# usbtomidi.net
KiCad netlist of a schematic drawn in EAGLE
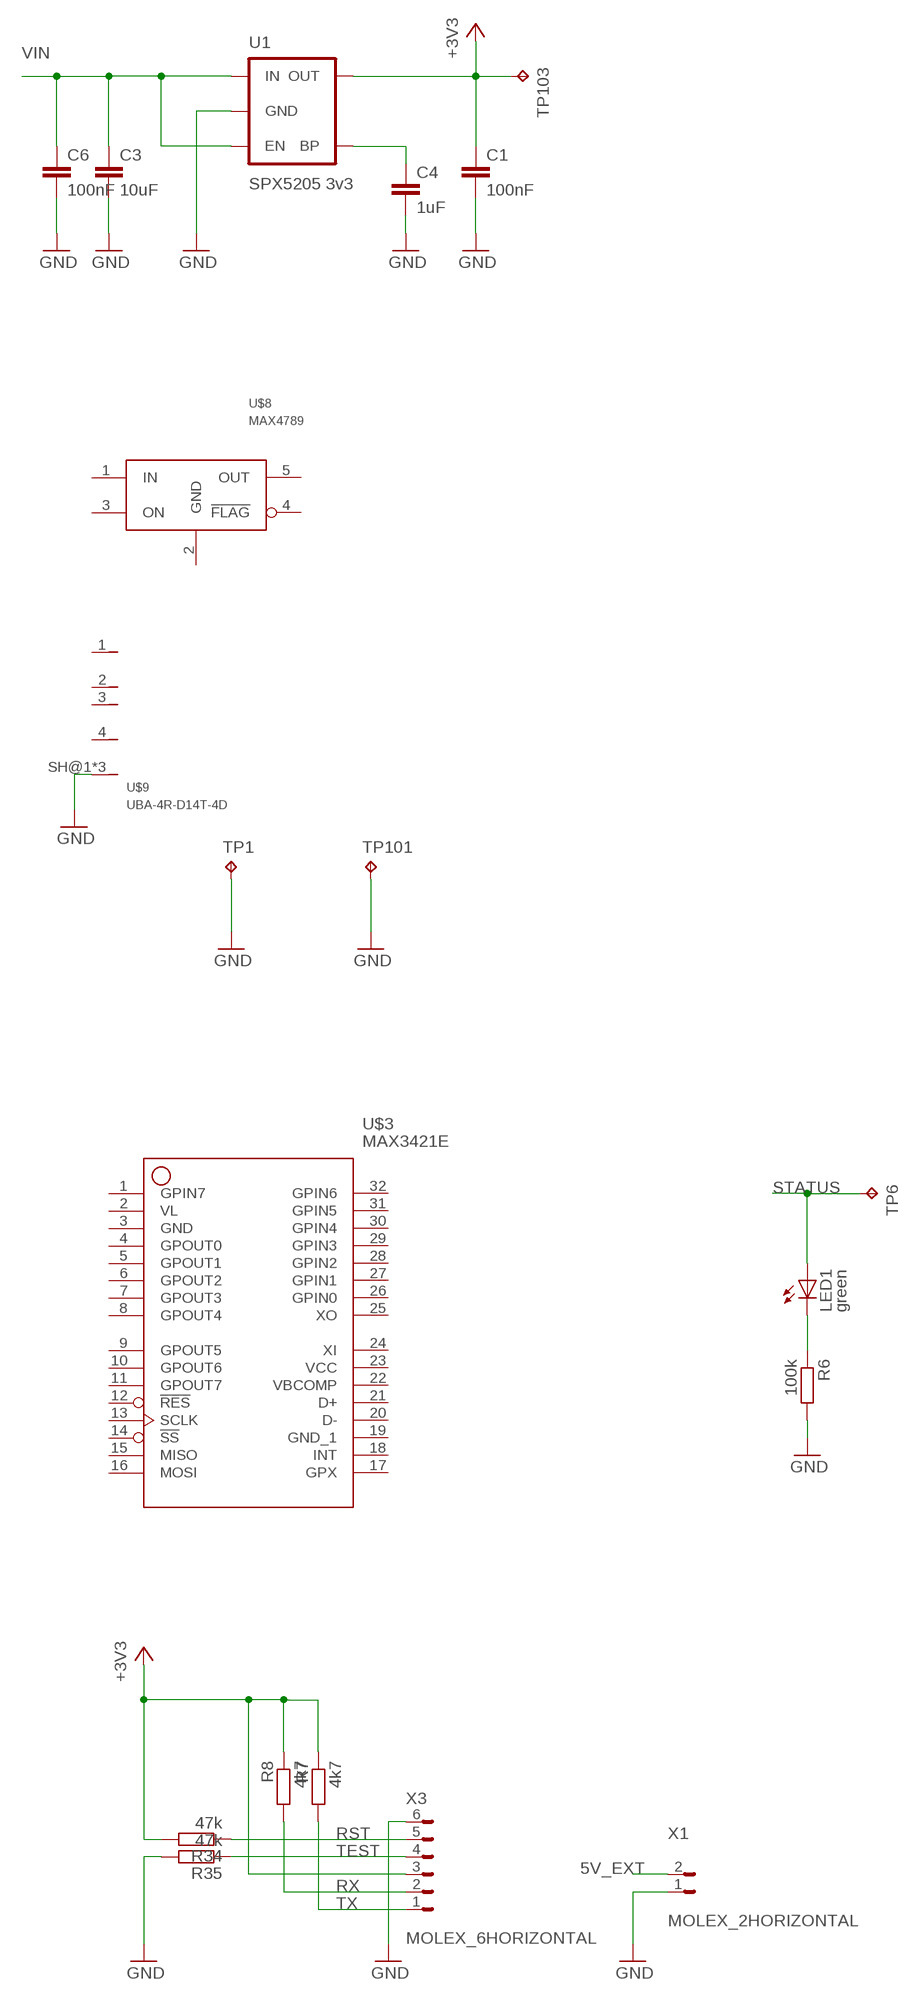
[diagram p0: schematic, sheet 1, part 1 of 2]
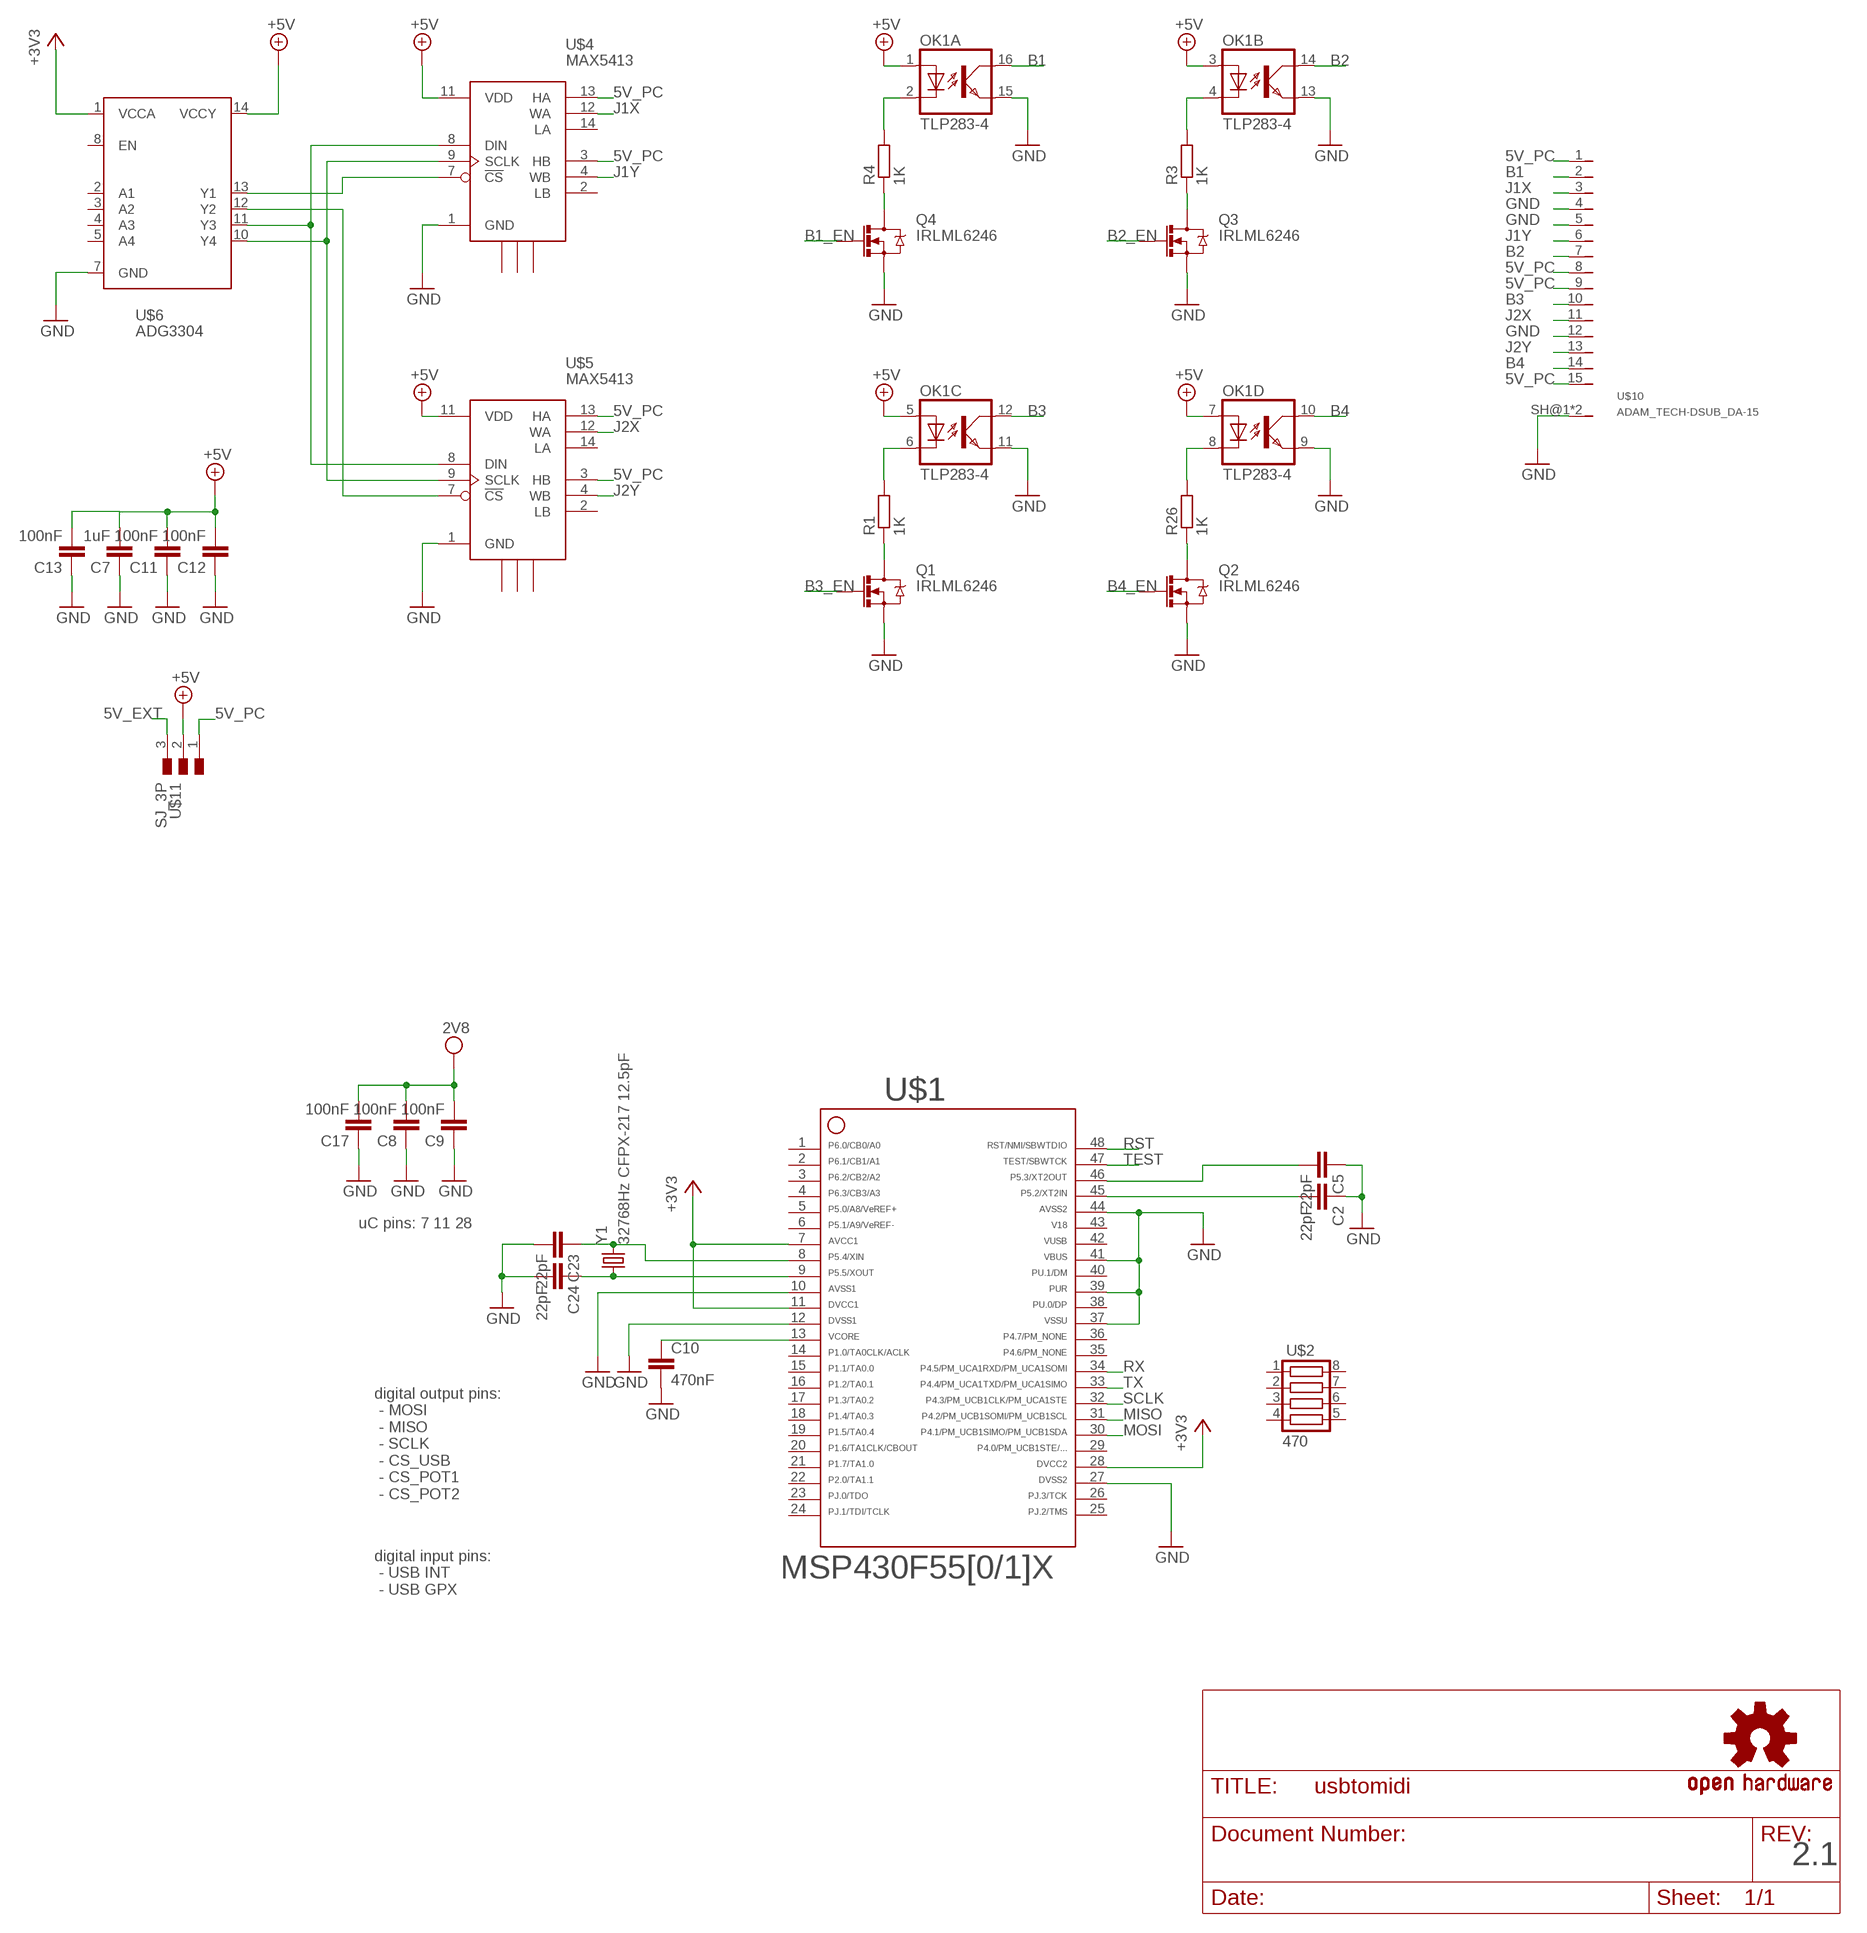
[diagram p1: schematic, sheet 1, part 2 of 2]

(export (version "E")
  (design (tool "Eeschema 10.0.6"))
  (components
    (comp (ref "C1")
      (value "100nF")
      (footprint "eagle-import:C0805")
      (libsource (lib "eagle-import") (part "C-EUC0805"))
    )
    (comp (ref "C2")
      (value "22pF")
      (footprint "eagle-import:C0805")
      (libsource (lib "eagle-import") (part "C-EUC0805"))
    )
    (comp (ref "C3")
      (value "10uF")
      (footprint "eagle-import:C0805")
      (libsource (lib "eagle-import") (part "C-EUC0805"))
    )
    (comp (ref "C4")
      (value "1uF")
      (footprint "eagle-import:C0805")
      (libsource (lib "eagle-import") (part "C-EUC0805"))
    )
    (comp (ref "C5")
      (value "22pF")
      (footprint "eagle-import:C0805")
      (libsource (lib "eagle-import") (part "C-EUC0805"))
    )
    (comp (ref "C6")
      (value "100nF")
      (footprint "eagle-import:C0805")
      (libsource (lib "eagle-import") (part "C-EUC0805"))
    )
    (comp (ref "C7")
      (value "1uF")
      (footprint "eagle-import:C0805")
      (libsource (lib "eagle-import") (part "C-EUC0805"))
    )
    (comp (ref "C8")
      (value "100nF")
      (footprint "eagle-import:C0805")
      (libsource (lib "eagle-import") (part "C-EUC0805"))
    )
    (comp (ref "C9")
      (value "100nF")
      (footprint "eagle-import:C0805")
      (libsource (lib "eagle-import") (part "C-EUC0805"))
    )
    (comp (ref "C10")
      (value "470nF")
      (footprint "eagle-import:C0805")
      (libsource (lib "eagle-import") (part "C-EUC0805"))
    )
    (comp (ref "C11")
      (value "100nF")
      (footprint "eagle-import:C0805")
      (libsource (lib "eagle-import") (part "C-EUC0805"))
    )
    (comp (ref "C12")
      (value "100nF")
      (footprint "eagle-import:C0805")
      (libsource (lib "eagle-import") (part "C-EUC0805"))
    )
    (comp (ref "C13")
      (value "100nF")
      (footprint "eagle-import:C0805")
      (libsource (lib "eagle-import") (part "C-EUC0805"))
    )
    (comp (ref "C17")
      (value "100nF")
      (footprint "eagle-import:C0805")
      (libsource (lib "eagle-import") (part "C-EUC0805"))
    )
    (comp (ref "C23")
      (value "22pF")
      (footprint "eagle-import:C0805")
      (libsource (lib "eagle-import") (part "C-EUC0805"))
    )
    (comp (ref "C24")
      (value "22pF")
      (footprint "eagle-import:C0805")
      (libsource (lib "eagle-import") (part "C-EUC0805"))
    )
    (comp (ref "LED1")
      (value "green")
      (footprint "eagle-import:CHIPLED_0805")
      (libsource (lib "eagle-import") (part "LEDCHIPLED_0805"))
    )
    (comp (ref "OK1")
      (value "TLP283-4")
      (footprint "eagle-import:MINI-FLAT-16")
      (libsource (lib "eagle-import") (part "TLP283-4"))
    )
    (comp (ref "Q1")
      (value "IRLML6246")
      (footprint "eagle-import:SOT23-3")
      (libsource (lib "eagle-import") (part "MOSFET-NCHANNEL_SOT23-3"))
    )
    (comp (ref "Q2")
      (value "IRLML6246")
      (footprint "eagle-import:SOT23-3")
      (libsource (lib "eagle-import") (part "MOSFET-NCHANNEL_SOT23-3"))
    )
    (comp (ref "Q3")
      (value "IRLML6246")
      (footprint "eagle-import:SOT23-3")
      (libsource (lib "eagle-import") (part "MOSFET-NCHANNEL_SOT23-3"))
    )
    (comp (ref "Q4")
      (value "IRLML6246")
      (footprint "eagle-import:SOT23-3")
      (libsource (lib "eagle-import") (part "MOSFET-NCHANNEL_SOT23-3"))
    )
    (comp (ref "R1")
      (value "1K")
      (footprint "eagle-import:R0805W")
      (libsource (lib "eagle-import") (part "R-EU_R0805W"))
    )
    (comp (ref "R3")
      (value "1K")
      (footprint "eagle-import:R0805W")
      (libsource (lib "eagle-import") (part "R-EU_R0805W"))
    )
    (comp (ref "R4")
      (value "1K")
      (footprint "eagle-import:R0805W")
      (libsource (lib "eagle-import") (part "R-EU_R0805W"))
    )
    (comp (ref "R6")
      (value "100k")
      (footprint "eagle-import:R0805W")
      (libsource (lib "eagle-import") (part "R-EU_R0805W"))
    )
    (comp (ref "R7")
      (value "4k7")
      (footprint "eagle-import:R0805W")
      (libsource (lib "eagle-import") (part "R-EU_R0805W"))
    )
    (comp (ref "R8")
      (value "4k7")
      (footprint "eagle-import:R0805W")
      (libsource (lib "eagle-import") (part "R-EU_R0805W"))
    )
    (comp (ref "R26")
      (value "1K")
      (footprint "eagle-import:R0805W")
      (libsource (lib "eagle-import") (part "R-EU_R0805W"))
    )
    (comp (ref "R34")
      (value "47k")
      (footprint "eagle-import:R0805W")
      (libsource (lib "eagle-import") (part "R-EU_R0805W"))
    )
    (comp (ref "R35")
      (value "47k")
      (footprint "eagle-import:R0805W")
      (libsource (lib "eagle-import") (part "R-EU_R0805W"))
    )
    (comp (ref "TP1")
      (value "TPTP12R")
      (footprint "eagle-import:TP12R")
      (libsource (lib "eagle-import") (part "TPTP12R"))
    )
    (comp (ref "TP6")
      (value "TPTP12R")
      (footprint "eagle-import:TP12R")
      (libsource (lib "eagle-import") (part "TPTP12R"))
    )
    (comp (ref "TP101")
      (value "TPTP12R")
      (footprint "eagle-import:TP12R")
      (libsource (lib "eagle-import") (part "TPTP12R"))
    )
    (comp (ref "TP103")
      (value "TPTP12R")
      (footprint "eagle-import:TP12R")
      (libsource (lib "eagle-import") (part "TPTP12R"))
    )
    (comp (ref "U$1")
      (value "MSP430F5510")
      (footprint "eagle-import:PT48")
      (libsource (lib "eagle-import") (part "F55[0/1]X---PT48"))
    )
    (comp (ref "U$2")
      (value "470")
      (footprint "eagle-import:YC164")
      (libsource (lib "eagle-import") (part "RES_ARR"))
    )
    (comp (ref "U$3")
      (value "MAX3421E")
      (footprint "eagle-import:TQFP32")
      (libsource (lib "eagle-import") (part "MAX3421E"))
    )
    (comp (ref "U$4")
      (value "MAX5413")
      (footprint "eagle-import:TSSOP14")
      (libsource (lib "eagle-import") (part "MAX5413"))
    )
    (comp (ref "U$5")
      (value "MAX5413")
      (footprint "eagle-import:TSSOP14")
      (libsource (lib "eagle-import") (part "MAX5413"))
    )
    (comp (ref "U$6")
      (value "ADG3304")
      (footprint "eagle-import:TSSOP14")
      (libsource (lib "eagle-import") (part "ADG3304"))
    )
    (comp (ref "U$7")
      (value "OSHW-LOGOM")
      (footprint "eagle-import:OSHW-LOGO-M")
      (libsource (lib "eagle-import") (part "OSHW-LOGOM"))
    )
    (comp (ref "U$8")
      (value "MAX4789")
      (footprint "eagle-import:SOT23-5")
      (libsource (lib "eagle-import") (part "MAX4789"))
    )
    (comp (ref "U$9")
      (value "UBA-4R-D14T-4D")
      (footprint "eagle-import:UBA-4R-D14T-4D")
      (libsource (lib "eagle-import") (part "UBA-4R-D14T-4D"))
    )
    (comp (ref "U$10")
      (value "ADAM_TECH-DSUB_DA-15")
      (footprint "eagle-import:ADAM_TECH_D-SUB_15")
      (libsource (lib "eagle-import") (part "ADAM_TECH-DSUB_DA-15"))
    )
    (comp (ref "U$11")
      (value "SJ_3P")
      (footprint "eagle-import:SJ_3P")
      (libsource (lib "eagle-import") (part "SJ_3P"))
    )
    (comp (ref "U1")
      (value "SPX5205 3v3")
      (footprint "eagle-import:SOT23-5")
      (libsource (lib "eagle-import") (part "V_REG_LDOSMD"))
    )
    (comp (ref "X1")
      (value "MOLEX_2HORIZONTAL")
      (footprint "eagle-import:0530480210")
      (libsource (lib "eagle-import") (part "MOLEX_2HORIZONTAL"))
    )
    (comp (ref "X3")
      (value "MOLEX_6HORIZONTAL")
      (footprint "eagle-import:0530480610")
      (libsource (lib "eagle-import") (part "MOLEX_6HORIZONTAL"))
    )
    (comp (ref "Y1")
      (value "32768Hz CFPX-217 12.5pF")
      (footprint "eagle-import:CRYSTAL-SMD-3.2X1.5")
      (libsource (lib "eagle-import") (part "CRYSTAL3.2X1.5"))
    )
  )
  (nets
    (net (code "1") (name "+3V3") (class "Default")
      (node (ref "C1") (pin "1") (pinfunction "1_1") (pintype "passive"))
      (node (ref "R34") (pin "2") (pinfunction "2_2") (pintype "passive"))
      (node (ref "R7") (pin "1") (pinfunction "1_1") (pintype "passive"))
      (node (ref "R8") (pin "1") (pinfunction "1_1") (pintype "passive"))
      (node (ref "TP103") (pin "TP") (pinfunction "TP_TP") (pintype "input"))
      (node (ref "U$1") (pin "11") (pinfunction "11_11") (pintype "power_in"))
      (node (ref "U$1") (pin "28") (pinfunction "28_28") (pintype "power_in"))
      (node (ref "U$1") (pin "7") (pinfunction "7_7") (pintype "power_in"))
      (node (ref "U$6") (pin "1") (pinfunction "VCCA_1") (pintype "bidirectional"))
      (node (ref "U1") (pin "5") (pinfunction "OUT_5") (pintype "passive"))
      (node (ref "X3") (pin "3") (pinfunction "4_3") (pintype "passive"))
    )
    (net (code "2") (name "+5V") (class "Default")
      (node (ref "C11") (pin "2") (pinfunction "2_2") (pintype "passive"))
      (node (ref "C12") (pin "2") (pinfunction "2_2") (pintype "passive"))
      (node (ref "C13") (pin "2") (pinfunction "2_2") (pintype "passive"))
      (node (ref "C7") (pin "2") (pinfunction "2_2") (pintype "passive"))
      (node (ref "OK1") (pin "1") (pinfunction "A_1") (pintype "passive"))
      (node (ref "OK1") (pin "3") (pinfunction "A_3") (pintype "passive"))
      (node (ref "OK1") (pin "5") (pinfunction "A_5") (pintype "passive"))
      (node (ref "OK1") (pin "7") (pinfunction "A_7") (pintype "passive"))
      (node (ref "U$11") (pin "2") (pinfunction "2_2") (pintype "passive"))
      (node (ref "U$4") (pin "11") (pinfunction "VDD_11") (pintype "bidirectional"))
      (node (ref "U$5") (pin "11") (pinfunction "VDD_11") (pintype "bidirectional"))
      (node (ref "U$6") (pin "14") (pinfunction "VCCY_14") (pintype "bidirectional"))
    )
    (net (code "3") (name "/5V_EXT") (class "Default")
      (node (ref "U$11") (pin "3") (pinfunction "3_3") (pintype "passive"))
      (node (ref "X1") (pin "2") (pinfunction "1_2") (pintype "passive"))
    )
    (net (code "4") (name "/5V_PC") (class "Default")
      (node (ref "U$10") (pin "1") (pinfunction "1_1") (pintype "bidirectional"))
      (node (ref "U$10") (pin "15") (pinfunction "15_15") (pintype "bidirectional"))
      (node (ref "U$10") (pin "8") (pinfunction "8_8") (pintype "bidirectional"))
      (node (ref "U$10") (pin "9") (pinfunction "9_9") (pintype "bidirectional"))
      (node (ref "U$11") (pin "1") (pinfunction "1_1") (pintype "passive"))
      (node (ref "U$4") (pin "13") (pinfunction "HA_13") (pintype "bidirectional"))
      (node (ref "U$4") (pin "3") (pinfunction "HB_3") (pintype "bidirectional"))
      (node (ref "U$5") (pin "13") (pinfunction "HA_13") (pintype "bidirectional"))
      (node (ref "U$5") (pin "3") (pinfunction "HB_3") (pintype "bidirectional"))
    )
    (net (code "5") (name "/42") (class "Default")
      (node (ref "U$1") (pin "42") (pinfunction "42_42") (pintype "power_in"))
    )
    (net (code "6") (name "/43") (class "Default")
      (node (ref "U$1") (pin "43") (pinfunction "43_43") (pintype "power_in"))
    )
    (net (code "7") (name "/B1") (class "Default")
      (node (ref "OK1") (pin "16") (pinfunction "COL_16") (pintype "passive"))
      (node (ref "U$10") (pin "2") (pinfunction "2_2") (pintype "bidirectional"))
    )
    (net (code "8") (name "/B1_EN") (class "Default")
      (node (ref "Q4") (pin "1") (pinfunction "G_1") (pintype "passive"))
    )
    (net (code "9") (name "/B2") (class "Default")
      (node (ref "OK1") (pin "14") (pinfunction "COL_14") (pintype "passive"))
      (node (ref "U$10") (pin "7") (pinfunction "7_7") (pintype "bidirectional"))
    )
    (net (code "10") (name "/B2_EN") (class "Default")
      (node (ref "Q3") (pin "1") (pinfunction "G_1") (pintype "passive"))
    )
    (net (code "11") (name "/B3") (class "Default")
      (node (ref "OK1") (pin "12") (pinfunction "COL_12") (pintype "passive"))
      (node (ref "U$10") (pin "10") (pinfunction "10_10") (pintype "bidirectional"))
    )
    (net (code "12") (name "/B3_EN") (class "Default")
      (node (ref "Q1") (pin "1") (pinfunction "G_1") (pintype "passive"))
    )
    (net (code "13") (name "/B4") (class "Default")
      (node (ref "OK1") (pin "10") (pinfunction "COL_10") (pintype "passive"))
      (node (ref "U$10") (pin "14") (pinfunction "14_14") (pintype "bidirectional"))
    )
    (net (code "14") (name "/B4_EN") (class "Default")
      (node (ref "Q2") (pin "1") (pinfunction "G_1") (pintype "passive"))
    )
    (net (code "15") (name "/IN") (class "Default")
      (node (ref "U$8") (pin "1") (pinfunction "IN_1") (pintype "power_in"))
    )
    (net (code "16") (name "/J1X") (class "Default")
      (node (ref "U$10") (pin "3") (pinfunction "3_3") (pintype "bidirectional"))
      (node (ref "U$4") (pin "12") (pinfunction "WA_12") (pintype "bidirectional"))
    )
    (net (code "17") (name "/J1Y") (class "Default")
      (node (ref "U$10") (pin "6") (pinfunction "6_6") (pintype "bidirectional"))
      (node (ref "U$4") (pin "4") (pinfunction "WB_4") (pintype "bidirectional"))
    )
    (net (code "18") (name "/J2X") (class "Default")
      (node (ref "U$10") (pin "11") (pinfunction "11_11") (pintype "bidirectional"))
      (node (ref "U$5") (pin "12") (pinfunction "WA_12") (pintype "bidirectional"))
    )
    (net (code "19") (name "/J2Y") (class "Default")
      (node (ref "U$10") (pin "13") (pinfunction "13_13") (pintype "bidirectional"))
      (node (ref "U$5") (pin "4") (pinfunction "WB_4") (pintype "bidirectional"))
    )
    (net (code "20") (name "/MISO") (class "Default")
      (node (ref "U$1") (pin "31") (pinfunction "31_31") (pintype "bidirectional"))
    )
    (net (code "21") (name "/MOSI") (class "Default")
      (node (ref "U$1") (pin "30") (pinfunction "30_30") (pintype "bidirectional"))
    )
    (net (code "22") (name "/OUT") (class "Default")
      (node (ref "U$8") (pin "5") (pinfunction "OUT_5") (pintype "power_in"))
    )
    (net (code "23") (name "/RST") (class "Default")
      (node (ref "R34") (pin "1") (pinfunction "1_1") (pintype "passive"))
      (node (ref "U$1") (pin "48") (pinfunction "48_48") (pintype "bidirectional"))
      (node (ref "X3") (pin "5") (pinfunction "2_5") (pintype "passive"))
    )
    (net (code "24") (name "/RX") (class "Default")
      (node (ref "R8") (pin "2") (pinfunction "2_2") (pintype "passive"))
      (node (ref "U$1") (pin "34") (pinfunction "34_34") (pintype "bidirectional"))
      (node (ref "X3") (pin "2") (pinfunction "5_2") (pintype "passive"))
    )
    (net (code "25") (name "/SCLK") (class "Default")
      (node (ref "U$1") (pin "32") (pinfunction "32_32") (pintype "bidirectional"))
    )
    (net (code "26") (name "/STATUS") (class "Default")
      (node (ref "LED1") (pin "A") (pinfunction "A_A") (pintype "passive"))
      (node (ref "TP6") (pin "TP") (pinfunction "TP_TP") (pintype "input"))
    )
    (net (code "27") (name "/TEST") (class "Default")
      (node (ref "R35") (pin "1") (pinfunction "1_1") (pintype "passive"))
      (node (ref "U$1") (pin "47") (pinfunction "47_47") (pintype "input"))
      (node (ref "X3") (pin "4") (pinfunction "3_4") (pintype "passive"))
    )
    (net (code "28") (name "/TX") (class "Default")
      (node (ref "R7") (pin "2") (pinfunction "2_2") (pintype "passive"))
      (node (ref "U$1") (pin "33") (pinfunction "33_33") (pintype "bidirectional"))
      (node (ref "X3") (pin "1") (pinfunction "6_1") (pintype "passive"))
    )
    (net (code "29") (name "/VIN") (class "Default")
      (node (ref "C3") (pin "1") (pinfunction "1_1") (pintype "passive"))
      (node (ref "C6") (pin "1") (pinfunction "1_1") (pintype "passive"))
      (node (ref "U1") (pin "1") (pinfunction "IN_1") (pintype "input"))
      (node (ref "U1") (pin "3") (pinfunction "EN_3") (pintype "input"))
    )
    (net (code "30") (name "2V8") (class "Default")
      (node (ref "C17") (pin "2") (pinfunction "2_2") (pintype "passive"))
      (node (ref "C8") (pin "2") (pinfunction "2_2") (pintype "passive"))
      (node (ref "C9") (pin "2") (pinfunction "2_2") (pintype "passive"))
    )
    (net (code "31") (name "GND") (class "Default")
      (node (ref "C1") (pin "2") (pinfunction "2_2") (pintype "passive"))
      (node (ref "C10") (pin "2") (pinfunction "2_2") (pintype "passive"))
      (node (ref "C11") (pin "1") (pinfunction "1_1") (pintype "passive"))
      (node (ref "C12") (pin "1") (pinfunction "1_1") (pintype "passive"))
      (node (ref "C13") (pin "1") (pinfunction "1_1") (pintype "passive"))
      (node (ref "C17") (pin "1") (pinfunction "1_1") (pintype "passive"))
      (node (ref "C2") (pin "1") (pinfunction "1_1") (pintype "passive"))
      (node (ref "C23") (pin "2") (pinfunction "2_2") (pintype "passive"))
      (node (ref "C24") (pin "2") (pinfunction "2_2") (pintype "passive"))
      (node (ref "C3") (pin "2") (pinfunction "2_2") (pintype "passive"))
      (node (ref "C4") (pin "2") (pinfunction "2_2") (pintype "passive"))
      (node (ref "C5") (pin "1") (pinfunction "1_1") (pintype "passive"))
      (node (ref "C6") (pin "2") (pinfunction "2_2") (pintype "passive"))
      (node (ref "C7") (pin "1") (pinfunction "1_1") (pintype "passive"))
      (node (ref "C8") (pin "1") (pinfunction "1_1") (pintype "passive"))
      (node (ref "C9") (pin "1") (pinfunction "1_1") (pintype "passive"))
      (node (ref "OK1") (pin "11") (pinfunction "EMIT_11") (pintype "passive"))
      (node (ref "OK1") (pin "13") (pinfunction "EMIT_13") (pintype "passive"))
      (node (ref "OK1") (pin "15") (pinfunction "EMIT_15") (pintype "passive"))
      (node (ref "OK1") (pin "9") (pinfunction "EMIT_9") (pintype "passive"))
      (node (ref "Q1") (pin "2") (pinfunction "S_2") (pintype "passive"))
      (node (ref "Q2") (pin "2") (pinfunction "S_2") (pintype "passive"))
      (node (ref "Q3") (pin "2") (pinfunction "S_2") (pintype "passive"))
      (node (ref "Q4") (pin "2") (pinfunction "S_2") (pintype "passive"))
      (node (ref "R35") (pin "2") (pinfunction "2_2") (pintype "passive"))
      (node (ref "R6") (pin "2") (pinfunction "2_2") (pintype "passive"))
      (node (ref "TP1") (pin "TP") (pinfunction "TP_TP") (pintype "input"))
      (node (ref "TP101") (pin "TP") (pinfunction "TP_TP") (pintype "input"))
      (node (ref "U$1") (pin "10") (pinfunction "10_10") (pintype "power_in"))
      (node (ref "U$1") (pin "12") (pinfunction "12_12") (pintype "power_in"))
      (node (ref "U$1") (pin "27") (pinfunction "27_27") (pintype "power_in"))
      (node (ref "U$1") (pin "37") (pinfunction "37_37") (pintype "power_in"))
      (node (ref "U$1") (pin "39") (pinfunction "39_39") (pintype "bidirectional"))
      (node (ref "U$1") (pin "41") (pinfunction "41_41") (pintype "power_in"))
      (node (ref "U$1") (pin "44") (pinfunction "44_44") (pintype "power_in"))
      (node (ref "U$10") (pin "12") (pinfunction "12_12") (pintype "bidirectional"))
      (node (ref "U$10") (pin "4") (pinfunction "4_4") (pintype "bidirectional"))
      (node (ref "U$10") (pin "5") (pinfunction "5_5") (pintype "bidirectional"))
      (node (ref "U$10") (pin "SH@1") (pinfunction "SHIELD_SH@1") (pintype "bidirectional"))
      (node (ref "U$10") (pin "SH@2") (pinfunction "SHIELD_SH@2") (pintype "bidirectional"))
      (node (ref "U$4") (pin "1") (pinfunction "GND_1") (pintype "bidirectional"))
      (node (ref "U$5") (pin "1") (pinfunction "GND_1") (pintype "bidirectional"))
      (node (ref "U$6") (pin "7") (pinfunction "GND_7") (pintype "bidirectional"))
      (node (ref "U$9") (pin "SH@1") (pinfunction "SH_SH@1") (pintype "bidirectional"))
      (node (ref "U$9") (pin "SH@2") (pinfunction "SH_SH@2") (pintype "bidirectional"))
      (node (ref "U$9") (pin "SH@3") (pinfunction "SH_SH@3") (pintype "bidirectional"))
      (node (ref "U1") (pin "2") (pinfunction "GND_2") (pintype "input"))
      (node (ref "X1") (pin "1") (pinfunction "2_1") (pintype "passive"))
      (node (ref "X3") (pin "6") (pinfunction "1_6") (pintype "passive"))
    )
    (net (code "32") (name "Net-(C2-Pad2)") (class "Default")
      (node (ref "C2") (pin "2") (pinfunction "2_2") (pintype "passive"))
      (node (ref "U$1") (pin "45") (pinfunction "45_45") (pintype "bidirectional"))
    )
    (net (code "33") (name "Net-(C5-Pad2)") (class "Default")
      (node (ref "C5") (pin "2") (pinfunction "2_2") (pintype "passive"))
      (node (ref "U$1") (pin "46") (pinfunction "46_46") (pintype "power_in"))
    )
    (net (code "34") (name "Net-(C10-Pad1)") (class "Default")
      (node (ref "C10") (pin "1") (pinfunction "1_1") (pintype "passive"))
      (node (ref "U$1") (pin "13") (pinfunction "13_13") (pintype "power_in"))
    )
    (net (code "35") (name "Net-(LED1-PadC)") (class "Default")
      (node (ref "LED1") (pin "C") (pinfunction "C_C") (pintype "passive"))
      (node (ref "R6") (pin "1") (pinfunction "1_1") (pintype "passive"))
    )
    (net (code "36") (name "Net-(OK1A-C)") (class "Default")
      (node (ref "OK1") (pin "2") (pinfunction "C_2") (pintype "passive"))
      (node (ref "R4") (pin "2") (pinfunction "2_2") (pintype "passive"))
    )
    (net (code "37") (name "Net-(OK1B-C)") (class "Default")
      (node (ref "OK1") (pin "4") (pinfunction "C_4") (pintype "passive"))
      (node (ref "R3") (pin "2") (pinfunction "2_2") (pintype "passive"))
    )
    (net (code "38") (name "Net-(OK1C-C)") (class "Default")
      (node (ref "OK1") (pin "6") (pinfunction "C_6") (pintype "passive"))
      (node (ref "R1") (pin "2") (pinfunction "2_2") (pintype "passive"))
    )
    (net (code "39") (name "Net-(OK1D-C)") (class "Default")
      (node (ref "OK1") (pin "8") (pinfunction "C_8") (pintype "passive"))
      (node (ref "R26") (pin "2") (pinfunction "2_2") (pintype "passive"))
    )
    (net (code "40") (name "Net-(Q1-D)") (class "Default")
      (node (ref "Q1") (pin "3") (pinfunction "D_3") (pintype "passive"))
      (node (ref "R1") (pin "1") (pinfunction "1_1") (pintype "passive"))
    )
    (net (code "41") (name "Net-(Q2-D)") (class "Default")
      (node (ref "Q2") (pin "3") (pinfunction "D_3") (pintype "passive"))
      (node (ref "R26") (pin "1") (pinfunction "1_1") (pintype "passive"))
    )
    (net (code "42") (name "Net-(Q3-D)") (class "Default")
      (node (ref "Q3") (pin "3") (pinfunction "D_3") (pintype "passive"))
      (node (ref "R3") (pin "1") (pinfunction "1_1") (pintype "passive"))
    )
    (net (code "43") (name "Net-(Q4-D)") (class "Default")
      (node (ref "Q4") (pin "3") (pinfunction "D_3") (pintype "passive"))
      (node (ref "R4") (pin "1") (pinfunction "1_1") (pintype "passive"))
    )
    (net (code "44") (name "Net-(U$4-DIN)") (class "Default")
      (node (ref "U$4") (pin "8") (pinfunction "DIN_8") (pintype "input"))
      (node (ref "U$5") (pin "8") (pinfunction "DIN_8") (pintype "input"))
      (node (ref "U$6") (pin "11") (pinfunction "Y3_11") (pintype "bidirectional"))
    )
    (net (code "45") (name "Net-(U$4-SCLK)") (class "Default")
      (node (ref "U$4") (pin "9") (pinfunction "SCLK_9") (pintype "input"))
      (node (ref "U$5") (pin "9") (pinfunction "SCLK_9") (pintype "input"))
      (node (ref "U$6") (pin "10") (pinfunction "Y4_10") (pintype "bidirectional"))
    )
    (net (code "46") (name "Net-(U$4-~{CS})") (class "Default")
      (node (ref "U$4") (pin "7") (pinfunction "~{CS}_7") (pintype "input"))
      (node (ref "U$6") (pin "13") (pinfunction "Y1_13") (pintype "bidirectional"))
    )
    (net (code "47") (name "Net-(U$5-~{CS})") (class "Default")
      (node (ref "U$5") (pin "7") (pinfunction "~{CS}_7") (pintype "input"))
      (node (ref "U$6") (pin "12") (pinfunction "Y2_12") (pintype "bidirectional"))
    )
    (net (code "48") (name "Net-(U1-BP)") (class "Default")
      (node (ref "C4") (pin "1") (pinfunction "1_1") (pintype "passive"))
      (node (ref "U1") (pin "4") (pinfunction "BP_4") (pintype "input"))
    )
    (net (code "49") (name "Net-(Y1-1)") (class "Default")
      (node (ref "C24") (pin "1") (pinfunction "1_1") (pintype "passive"))
      (node (ref "U$1") (pin "9") (pinfunction "9_9") (pintype "bidirectional"))
      (node (ref "Y1") (pin "P$1") (pinfunction "1_P$1") (pintype "passive"))
    )
    (net (code "50") (name "Net-(Y1-2)") (class "Default")
      (node (ref "C23") (pin "1") (pinfunction "1_1") (pintype "passive"))
      (node (ref "U$1") (pin "8") (pinfunction "8_8") (pintype "bidirectional"))
      (node (ref "Y1") (pin "P$2") (pinfunction "2_P$2") (pintype "passive"))
    )
    (net (code "51") (name "unconnected-(U$1-Pad1)") (class "Default")
      (node (ref "U$1") (pin "1") (pinfunction "1_1") (pintype "bidirectional"))
    )
    (net (code "52") (name "unconnected-(U$1-Pad2)") (class "Default")
      (node (ref "U$1") (pin "2") (pinfunction "2_2") (pintype "bidirectional"))
    )
    (net (code "53") (name "unconnected-(U$1-Pad3)") (class "Default")
      (node (ref "U$1") (pin "3") (pinfunction "3_3") (pintype "bidirectional"))
    )
    (net (code "54") (name "unconnected-(U$1-Pad4)") (class "Default")
      (node (ref "U$1") (pin "4") (pinfunction "4_4") (pintype "bidirectional"))
    )
    (net (code "55") (name "unconnected-(U$1-Pad5)") (class "Default")
      (node (ref "U$1") (pin "5") (pinfunction "5_5") (pintype "bidirectional"))
    )
    (net (code "56") (name "unconnected-(U$1-Pad6)") (class "Default")
      (node (ref "U$1") (pin "6") (pinfunction "6_6") (pintype "bidirectional"))
    )
    (net (code "57") (name "unconnected-(U$1-Pad14)") (class "Default")
      (node (ref "U$1") (pin "14") (pinfunction "14_14") (pintype "bidirectional"))
    )
    (net (code "58") (name "unconnected-(U$1-Pad15)") (class "Default")
      (node (ref "U$1") (pin "15") (pinfunction "15_15") (pintype "bidirectional"))
    )
    (net (code "59") (name "unconnected-(U$1-Pad16)") (class "Default")
      (node (ref "U$1") (pin "16") (pinfunction "16_16") (pintype "bidirectional"))
    )
    (net (code "60") (name "unconnected-(U$1-Pad17)") (class "Default")
      (node (ref "U$1") (pin "17") (pinfunction "17_17") (pintype "bidirectional"))
    )
    (net (code "61") (name "unconnected-(U$1-Pad18)") (class "Default")
      (node (ref "U$1") (pin "18") (pinfunction "18_18") (pintype "bidirectional"))
    )
    (net (code "62") (name "unconnected-(U$1-Pad19)") (class "Default")
      (node (ref "U$1") (pin "19") (pinfunction "19_19") (pintype "bidirectional"))
    )
    (net (code "63") (name "unconnected-(U$1-Pad20)") (class "Default")
      (node (ref "U$1") (pin "20") (pinfunction "20_20") (pintype "bidirectional"))
    )
    (net (code "64") (name "unconnected-(U$1-Pad21)") (class "Default")
      (node (ref "U$1") (pin "21") (pinfunction "21_21") (pintype "bidirectional"))
    )
    (net (code "65") (name "unconnected-(U$1-Pad22)") (class "Default")
      (node (ref "U$1") (pin "22") (pinfunction "22_22") (pintype "bidirectional"))
    )
    (net (code "66") (name "unconnected-(U$1-Pad23)") (class "Default")
      (node (ref "U$1") (pin "23") (pinfunction "23_23") (pintype "bidirectional"))
    )
    (net (code "67") (name "unconnected-(U$1-Pad24)") (class "Default")
      (node (ref "U$1") (pin "24") (pinfunction "24_24") (pintype "bidirectional"))
    )
    (net (code "68") (name "unconnected-(U$1-Pad25)") (class "Default")
      (node (ref "U$1") (pin "25") (pinfunction "25_25") (pintype "bidirectional"))
    )
    (net (code "69") (name "unconnected-(U$1-Pad26)") (class "Default")
      (node (ref "U$1") (pin "26") (pinfunction "26_26") (pintype "bidirectional"))
    )
    (net (code "70") (name "unconnected-(U$1-Pad29)") (class "Default")
      (node (ref "U$1") (pin "29") (pinfunction "29_29") (pintype "bidirectional"))
    )
    (net (code "71") (name "unconnected-(U$1-Pad35)") (class "Default")
      (node (ref "U$1") (pin "35") (pinfunction "35_35") (pintype "bidirectional"))
    )
    (net (code "72") (name "unconnected-(U$1-Pad36)") (class "Default")
      (node (ref "U$1") (pin "36") (pinfunction "36_36") (pintype "bidirectional"))
    )
    (net (code "73") (name "unconnected-(U$1-Pad38)") (class "Default")
      (node (ref "U$1") (pin "38") (pinfunction "38_38") (pintype "bidirectional"))
    )
    (net (code "74") (name "unconnected-(U$1-Pad40)") (class "Default")
      (node (ref "U$1") (pin "40") (pinfunction "40_40") (pintype "bidirectional"))
    )
    (net (code "75") (name "unconnected-(U$2-Pad1)") (class "Default")
      (node (ref "U$2") (pin "1") (pinfunction "1_1") (pintype "passive"))
    )
    (net (code "76") (name "unconnected-(U$2-Pad2)") (class "Default")
      (node (ref "U$2") (pin "2") (pinfunction "2_2") (pintype "passive"))
    )
    (net (code "77") (name "unconnected-(U$2-Pad3)") (class "Default")
      (node (ref "U$2") (pin "3") (pinfunction "3_3") (pintype "passive"))
    )
    (net (code "78") (name "unconnected-(U$2-Pad4)") (class "Default")
      (node (ref "U$2") (pin "4") (pinfunction "4_4") (pintype "passive"))
    )
    (net (code "79") (name "unconnected-(U$2-Pad5)") (class "Default")
      (node (ref "U$2") (pin "5") (pinfunction "5_5") (pintype "passive"))
    )
    (net (code "80") (name "unconnected-(U$2-Pad6)") (class "Default")
      (node (ref "U$2") (pin "6") (pinfunction "6_6") (pintype "passive"))
    )
    (net (code "81") (name "unconnected-(U$2-Pad7)") (class "Default")
      (node (ref "U$2") (pin "7") (pinfunction "7_7") (pintype "passive"))
    )
    (net (code "82") (name "unconnected-(U$2-Pad8)") (class "Default")
      (node (ref "U$2") (pin "8") (pinfunction "8_8") (pintype "passive"))
    )
    (net (code "83") (name "unconnected-(U$3-D+-Pad21)") (class "Default")
      (node (ref "U$3") (pin "21") (pinfunction "D+_21") (pintype "bidirectional"))
    )
    (net (code "84") (name "unconnected-(U$3-D--Pad20)") (class "Default")
      (node (ref "U$3") (pin "20") (pinfunction "D-_20") (pintype "bidirectional"))
    )
    (net (code "85") (name "unconnected-(U$3-GND-Pad3)") (class "Default")
      (node (ref "U$3") (pin "3") (pinfunction "GND_3") (pintype "bidirectional"))
    )
    (net (code "86") (name "unconnected-(U$3-GND_1-Pad19)") (class "Default")
      (node (ref "U$3") (pin "19") (pinfunction "GND_1_19") (pintype "bidirectional"))
    )
    (net (code "87") (name "unconnected-(U$3-GPIN0-Pad26)") (class "Default")
      (node (ref "U$3") (pin "26") (pinfunction "GPIN0_26") (pintype "input"))
    )
    (net (code "88") (name "unconnected-(U$3-GPIN1-Pad27)") (class "Default")
      (node (ref "U$3") (pin "27") (pinfunction "GPIN1_27") (pintype "input"))
    )
    (net (code "89") (name "unconnected-(U$3-GPIN2-Pad28)") (class "Default")
      (node (ref "U$3") (pin "28") (pinfunction "GPIN2_28") (pintype "input"))
    )
    (net (code "90") (name "unconnected-(U$3-GPIN3-Pad29)") (class "Default")
      (node (ref "U$3") (pin "29") (pinfunction "GPIN3_29") (pintype "input"))
    )
    (net (code "91") (name "unconnected-(U$3-GPIN4-Pad30)") (class "Default")
      (node (ref "U$3") (pin "30") (pinfunction "GPIN4_30") (pintype "input"))
    )
    (net (code "92") (name "unconnected-(U$3-GPIN5-Pad31)") (class "Default")
      (node (ref "U$3") (pin "31") (pinfunction "GPIN5_31") (pintype "input"))
    )
    (net (code "93") (name "unconnected-(U$3-GPIN6-Pad32)") (class "Default")
      (node (ref "U$3") (pin "32") (pinfunction "GPIN6_32") (pintype "input"))
    )
    (net (code "94") (name "unconnected-(U$3-GPIN7-Pad1)") (class "Default")
      (node (ref "U$3") (pin "1") (pinfunction "GPIN7_1") (pintype "input"))
    )
    (net (code "95") (name "unconnected-(U$3-GPOUT0-Pad4)") (class "Default")
      (node (ref "U$3") (pin "4") (pinfunction "GPOUT0_4") (pintype "output"))
    )
    (net (code "96") (name "unconnected-(U$3-GPOUT1-Pad5)") (class "Default")
      (node (ref "U$3") (pin "5") (pinfunction "GPOUT1_5") (pintype "output"))
    )
    (net (code "97") (name "unconnected-(U$3-GPOUT2-Pad6)") (class "Default")
      (node (ref "U$3") (pin "6") (pinfunction "GPOUT2_6") (pintype "output"))
    )
    (net (code "98") (name "unconnected-(U$3-GPOUT3-Pad7)") (class "Default")
      (node (ref "U$3") (pin "7") (pinfunction "GPOUT3_7") (pintype "output"))
    )
    (net (code "99") (name "unconnected-(U$3-GPOUT4-Pad8)") (class "Default")
      (node (ref "U$3") (pin "8") (pinfunction "GPOUT4_8") (pintype "output"))
    )
    (net (code "100") (name "unconnected-(U$3-GPOUT5-Pad9)") (class "Default")
      (node (ref "U$3") (pin "9") (pinfunction "GPOUT5_9") (pintype "output"))
    )
    (net (code "101") (name "unconnected-(U$3-GPOUT6-Pad10)") (class "Default")
      (node (ref "U$3") (pin "10") (pinfunction "GPOUT6_10") (pintype "output"))
    )
    (net (code "102") (name "unconnected-(U$3-GPOUT7-Pad11)") (class "Default")
      (node (ref "U$3") (pin "11") (pinfunction "GPOUT7_11") (pintype "output"))
    )
    (net (code "103") (name "unconnected-(U$3-GPX-Pad17)") (class "Default")
      (node (ref "U$3") (pin "17") (pinfunction "GPX_17") (pintype "output"))
    )
    (net (code "104") (name "unconnected-(U$3-INT-Pad18)") (class "Default")
      (node (ref "U$3") (pin "18") (pinfunction "INT_18") (pintype "output"))
    )
    (net (code "105") (name "unconnected-(U$3-MISO-Pad15)") (class "Default")
      (node (ref "U$3") (pin "15") (pinfunction "MISO_15") (pintype "output"))
    )
    (net (code "106") (name "unconnected-(U$3-MOSI-Pad16)") (class "Default")
      (node (ref "U$3") (pin "16") (pinfunction "MOSI_16") (pintype "bidirectional"))
    )
    (net (code "107") (name "unconnected-(U$3-SCLK-Pad13)") (class "Default")
      (node (ref "U$3") (pin "13") (pinfunction "SCLK_13") (pintype "input"))
    )
    (net (code "108") (name "unconnected-(U$3-VBCOMP-Pad22)") (class "Default")
      (node (ref "U$3") (pin "22") (pinfunction "VBCOMP_22") (pintype "input"))
    )
    (net (code "109") (name "unconnected-(U$3-VCC-Pad23)") (class "Default")
      (node (ref "U$3") (pin "23") (pinfunction "VCC_23") (pintype "bidirectional"))
    )
    (net (code "110") (name "unconnected-(U$3-VL-Pad2)") (class "Default")
      (node (ref "U$3") (pin "2") (pinfunction "VL_2") (pintype "input"))
    )
    (net (code "111") (name "unconnected-(U$3-XI-Pad24)") (class "Default")
      (node (ref "U$3") (pin "24") (pinfunction "XI_24") (pintype "input"))
    )
    (net (code "112") (name "unconnected-(U$3-XO-Pad25)") (class "Default")
      (node (ref "U$3") (pin "25") (pinfunction "XO_25") (pintype "output"))
    )
    (net (code "113") (name "unconnected-(U$3-~{RES}-Pad12)") (class "Default")
      (node (ref "U$3") (pin "12") (pinfunction "~{RES}_12") (pintype "input"))
    )
    (net (code "114") (name "unconnected-(U$3-~{SS}-Pad14)") (class "Default")
      (node (ref "U$3") (pin "14") (pinfunction "~{SS}_14") (pintype "input"))
    )
    (net (code "115") (name "unconnected-(U$4-LA-Pad14)") (class "Default")
      (node (ref "U$4") (pin "14") (pinfunction "LA_14") (pintype "bidirectional"))
    )
    (net (code "116") (name "unconnected-(U$4-LB-Pad2)") (class "Default")
      (node (ref "U$4") (pin "2") (pinfunction "LB_2") (pintype "bidirectional"))
    )
    (net (code "117") (name "unconnected-(U$4-NC1-Pad5)") (class "Default")
      (node (ref "U$4") (pin "5") (pinfunction "NC1_5") (pintype "no_connect"))
    )
    (net (code "118") (name "unconnected-(U$4-NC2-Pad6)") (class "Default")
      (node (ref "U$4") (pin "6") (pinfunction "NC2_6") (pintype "no_connect"))
    )
    (net (code "119") (name "unconnected-(U$4-NC3-Pad10)") (class "Default")
      (node (ref "U$4") (pin "10") (pinfunction "NC3_10") (pintype "no_connect"))
    )
    (net (code "120") (name "unconnected-(U$5-LA-Pad14)") (class "Default")
      (node (ref "U$5") (pin "14") (pinfunction "LA_14") (pintype "bidirectional"))
    )
    (net (code "121") (name "unconnected-(U$5-LB-Pad2)") (class "Default")
      (node (ref "U$5") (pin "2") (pinfunction "LB_2") (pintype "bidirectional"))
    )
    (net (code "122") (name "unconnected-(U$5-NC1-Pad5)") (class "Default")
      (node (ref "U$5") (pin "5") (pinfunction "NC1_5") (pintype "no_connect"))
    )
    (net (code "123") (name "unconnected-(U$5-NC2-Pad6)") (class "Default")
      (node (ref "U$5") (pin "6") (pinfunction "NC2_6") (pintype "no_connect"))
    )
    (net (code "124") (name "unconnected-(U$5-NC3-Pad10)") (class "Default")
      (node (ref "U$5") (pin "10") (pinfunction "NC3_10") (pintype "no_connect"))
    )
    (net (code "125") (name "unconnected-(U$6-A1-Pad2)") (class "Default")
      (node (ref "U$6") (pin "2") (pinfunction "A1_2") (pintype "bidirectional"))
    )
    (net (code "126") (name "unconnected-(U$6-A2-Pad3)") (class "Default")
      (node (ref "U$6") (pin "3") (pinfunction "A2_3") (pintype "bidirectional"))
    )
    (net (code "127") (name "unconnected-(U$6-A3-Pad4)") (class "Default")
      (node (ref "U$6") (pin "4") (pinfunction "A3_4") (pintype "bidirectional"))
    )
    (net (code "128") (name "unconnected-(U$6-A4-Pad5)") (class "Default")
      (node (ref "U$6") (pin "5") (pinfunction "A4_5") (pintype "bidirectional"))
    )
    (net (code "129") (name "unconnected-(U$6-EN-Pad8)") (class "Default")
      (node (ref "U$6") (pin "8") (pinfunction "EN_8") (pintype "bidirectional"))
    )
    (net (code "130") (name "unconnected-(U$8-GND-Pad2)") (class "Default")
      (node (ref "U$8") (pin "2") (pinfunction "GND_2") (pintype "bidirectional"))
    )
    (net (code "131") (name "unconnected-(U$8-ON-Pad3)") (class "Default")
      (node (ref "U$8") (pin "3") (pinfunction "ON_3") (pintype "input"))
    )
    (net (code "132") (name "unconnected-(U$8-~{FLAG}-Pad4)") (class "Default")
      (node (ref "U$8") (pin "4") (pinfunction "~{FLAG}_4") (pintype "output"))
    )
    (net (code "133") (name "unconnected-(U$9-Pad1)") (class "Default")
      (node (ref "U$9") (pin "1") (pinfunction "1_1") (pintype "bidirectional"))
    )
    (net (code "134") (name "unconnected-(U$9-Pad2)") (class "Default")
      (node (ref "U$9") (pin "2") (pinfunction "2_2") (pintype "bidirectional"))
    )
    (net (code "135") (name "unconnected-(U$9-Pad3)") (class "Default")
      (node (ref "U$9") (pin "3") (pinfunction "3_3") (pintype "bidirectional"))
    )
    (net (code "136") (name "unconnected-(U$9-Pad4)") (class "Default")
      (node (ref "U$9") (pin "4") (pinfunction "4_4") (pintype "bidirectional"))
    )
  )
)
